# versao1b.net
KiCad netlist of a schematic drawn in EAGLE
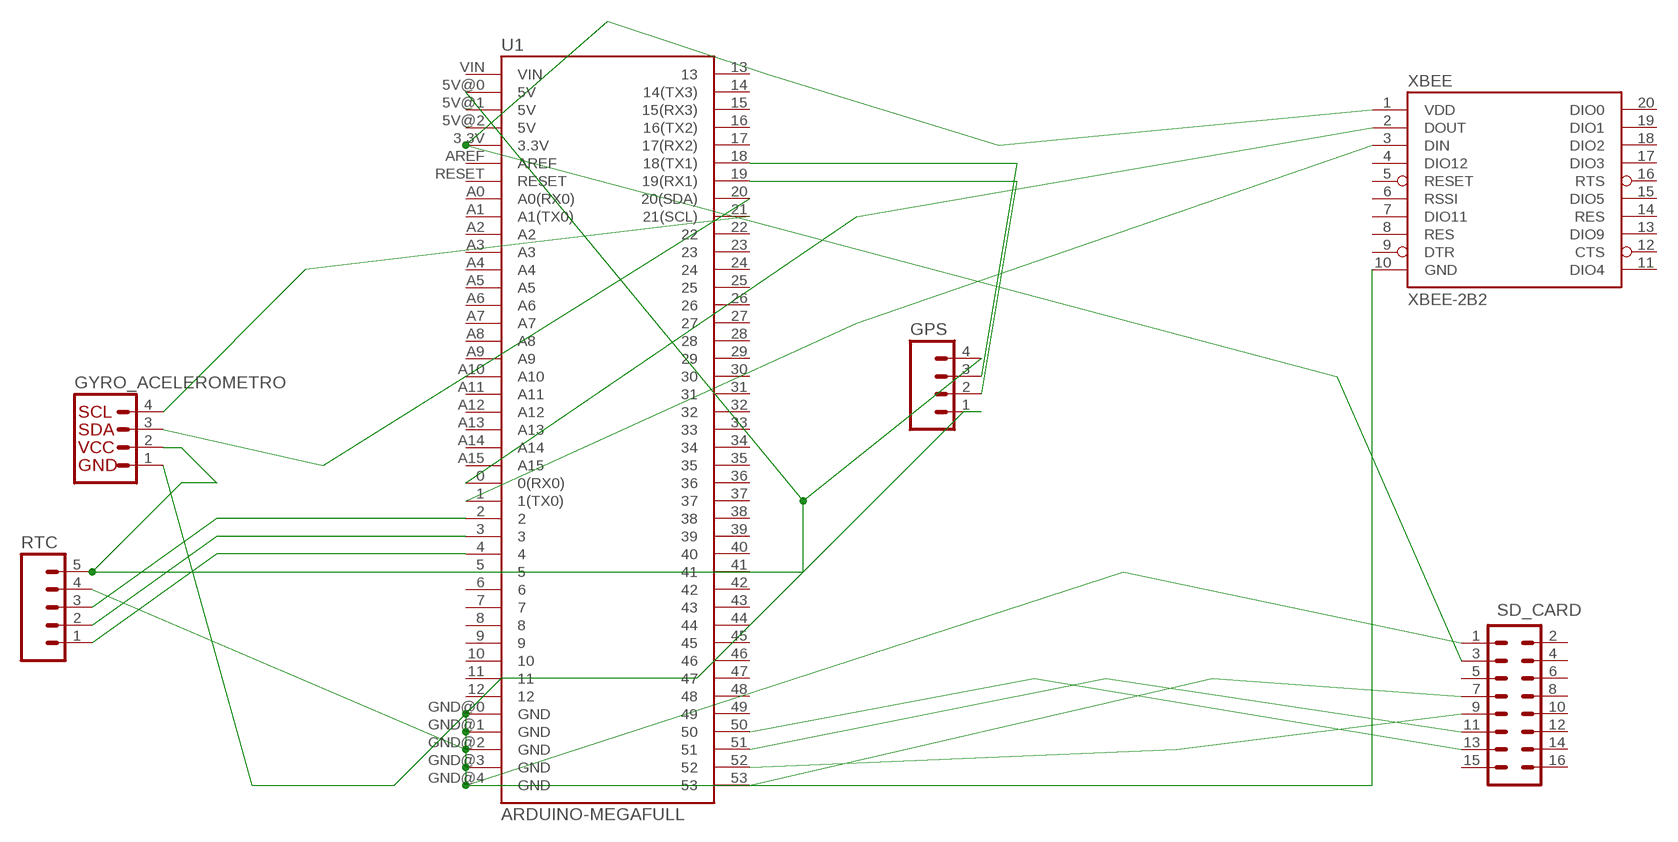
[diagram p0: schematic, sheet 1]

(export (version "E")
  (design (tool "Eeschema 10.0.6"))
  (components
    (comp (ref "GPS")
      (value "M04LOCK")
      (footprint "eagle-import:1X04_LOCK")
      (libsource (lib "eagle-import") (part "M04LOCK"))
    )
    (comp (ref "GYRO_ACELEROMETRO")
      (value "I2C_STANDARD")
      (footprint "eagle-import:1X04")
      (libsource (lib "eagle-import") (part "I2C_STANDARD"))
    )
    (comp (ref "RTC")
      (value "M05LOCK")
      (footprint "eagle-import:1X05_LOCK")
      (libsource (lib "eagle-import") (part "M05LOCK"))
    )
    (comp (ref "SD_CARD")
      (value "M08X2")
      (footprint "eagle-import:2X8")
      (libsource (lib "eagle-import") (part "M08X2"))
    )
    (comp (ref "U1")
      (value "ARDUINO-MEGAFULL")
      (footprint "eagle-import:ARDUINO_MEGA")
      (libsource (lib "eagle-import") (part "ARDUINO-MEGAFULL"))
    )
    (comp (ref "XBEE")
      (value "XBEE-2B2")
      (footprint "eagle-import:XBEE-SILK")
      (libsource (lib "eagle-import") (part "XBEE-2B2"))
    )
  )
  (nets
    (net (code "1") (name "Net-(GPS-Pad4)") (class "Default")
      (node (ref "GPS") (pin "4") (pinfunction "4_4") (pintype "passive"))
      (node (ref "GYRO_ACELEROMETRO") (pin "2") (pinfunction "2_2") (pintype "passive"))
      (node (ref "RTC") (pin "5") (pinfunction "5_5") (pintype "passive"))
      (node (ref "U1") (pin "5V@0") (pinfunction "5V_5V@0") (pintype "bidirectional"))
    )
    (net (code "2") (name "Net-(RTC-Pad1)") (class "Default")
      (node (ref "RTC") (pin "1") (pinfunction "1_1") (pintype "passive"))
      (node (ref "U1") (pin "4") (pinfunction "4_4") (pintype "bidirectional"))
    )
    (net (code "3") (name "Net-(RTC-Pad2)") (class "Default")
      (node (ref "RTC") (pin "2") (pinfunction "2_2") (pintype "passive"))
      (node (ref "U1") (pin "3") (pinfunction "3_3") (pintype "bidirectional"))
    )
    (net (code "4") (name "Net-(RTC-Pad3)") (class "Default")
      (node (ref "RTC") (pin "3") (pinfunction "3_3") (pintype "passive"))
      (node (ref "U1") (pin "2") (pinfunction "2_2") (pintype "bidirectional"))
    )
    (net (code "5") (name "Net-(SD_CARD-Pad7)") (class "Default")
      (node (ref "SD_CARD") (pin "7") (pinfunction "7_7") (pintype "passive"))
      (node (ref "U1") (pin "53") (pinfunction "53_53") (pintype "bidirectional"))
    )
    (net (code "6") (name "Net-(SD_CARD-Pad9)") (class "Default")
      (node (ref "SD_CARD") (pin "9") (pinfunction "9_9") (pintype "passive"))
      (node (ref "U1") (pin "52") (pinfunction "52_52") (pintype "bidirectional"))
    )
    (net (code "7") (name "Net-(SD_CARD-Pad11)") (class "Default")
      (node (ref "SD_CARD") (pin "11") (pinfunction "11_11") (pintype "passive"))
      (node (ref "U1") (pin "51") (pinfunction "51_51") (pintype "bidirectional"))
    )
    (net (code "8") (name "Net-(SD_CARD-Pad13)") (class "Default")
      (node (ref "SD_CARD") (pin "13") (pinfunction "13_13") (pintype "passive"))
      (node (ref "U1") (pin "50") (pinfunction "50_50") (pintype "bidirectional"))
    )
    (net (code "9") (name "Net-(U1-0(RX0))") (class "Default")
      (node (ref "U1") (pin "0") (pinfunction "0(RX0)_0") (pintype "bidirectional"))
      (node (ref "XBEE") (pin "2") (pinfunction "DOUT_2") (pintype "output"))
    )
    (net (code "10") (name "Net-(U1-1(TX0))") (class "Default")
      (node (ref "U1") (pin "1") (pinfunction "1(TX0)_1") (pintype "bidirectional"))
      (node (ref "XBEE") (pin "3") (pinfunction "DIN_3") (pintype "input"))
    )
    (net (code "11") (name "Net-(U1-18(TX1))") (class "Default")
      (node (ref "GPS") (pin "3") (pinfunction "3_3") (pintype "passive"))
      (node (ref "U1") (pin "18") (pinfunction "18(TX1)_18") (pintype "bidirectional"))
    )
    (net (code "12") (name "Net-(U1-19(RX1))") (class "Default")
      (node (ref "GPS") (pin "2") (pinfunction "2_2") (pintype "passive"))
      (node (ref "U1") (pin "19") (pinfunction "19(RX1)_19") (pintype "bidirectional"))
    )
    (net (code "13") (name "Net-(U1-20(SDA))") (class "Default")
      (node (ref "GYRO_ACELEROMETRO") (pin "3") (pinfunction "3_3") (pintype "passive"))
      (node (ref "U1") (pin "20") (pinfunction "20(SDA)_20") (pintype "bidirectional"))
    )
    (net (code "14") (name "Net-(U1-21(SCL))") (class "Default")
      (node (ref "GYRO_ACELEROMETRO") (pin "4") (pinfunction "4_4") (pintype "passive"))
      (node (ref "U1") (pin "21") (pinfunction "21(SCL)_21") (pintype "bidirectional"))
    )
    (net (code "15") (name "Net-(XBEE-GND)") (class "Default")
      (node (ref "GPS") (pin "1") (pinfunction "1_1") (pintype "passive"))
      (node (ref "GYRO_ACELEROMETRO") (pin "1") (pinfunction "1_1") (pintype "passive"))
      (node (ref "RTC") (pin "4") (pinfunction "4_4") (pintype "passive"))
      (node (ref "SD_CARD") (pin "1") (pinfunction "1_1") (pintype "passive"))
      (node (ref "U1") (pin "GND@0") (pinfunction "GND_GND@0") (pintype "bidirectional"))
      (node (ref "U1") (pin "GND@1") (pinfunction "GND_GND@1") (pintype "bidirectional"))
      (node (ref "U1") (pin "GND@2") (pinfunction "GND_GND@2") (pintype "bidirectional"))
      (node (ref "U1") (pin "GND@3") (pinfunction "GND_GND@3") (pintype "bidirectional"))
      (node (ref "U1") (pin "GND@4") (pinfunction "GND_GND@4") (pintype "bidirectional"))
      (node (ref "XBEE") (pin "10") (pinfunction "GND_10") (pintype "power_in"))
    )
    (net (code "16") (name "Net-(XBEE-VDD)") (class "Default")
      (node (ref "SD_CARD") (pin "3") (pinfunction "3_3") (pintype "passive"))
      (node (ref "U1") (pin "3.3V") (pinfunction "3.3V_3.3V") (pintype "bidirectional"))
      (node (ref "XBEE") (pin "1") (pinfunction "VDD_1") (pintype "power_in"))
    )
    (net (code "17") (name "unconnected-(SD_CARD-Pad2)") (class "Default")
      (node (ref "SD_CARD") (pin "2") (pinfunction "2_2") (pintype "passive"))
    )
    (net (code "18") (name "unconnected-(SD_CARD-Pad4)") (class "Default")
      (node (ref "SD_CARD") (pin "4") (pinfunction "4_4") (pintype "passive"))
    )
    (net (code "19") (name "unconnected-(SD_CARD-Pad5)") (class "Default")
      (node (ref "SD_CARD") (pin "5") (pinfunction "5_5") (pintype "passive"))
    )
    (net (code "20") (name "unconnected-(SD_CARD-Pad6)") (class "Default")
      (node (ref "SD_CARD") (pin "6") (pinfunction "6_6") (pintype "passive"))
    )
    (net (code "21") (name "unconnected-(SD_CARD-Pad8)") (class "Default")
      (node (ref "SD_CARD") (pin "8") (pinfunction "8_8") (pintype "passive"))
    )
    (net (code "22") (name "unconnected-(SD_CARD-Pad10)") (class "Default")
      (node (ref "SD_CARD") (pin "10") (pinfunction "10_10") (pintype "passive"))
    )
    (net (code "23") (name "unconnected-(SD_CARD-Pad12)") (class "Default")
      (node (ref "SD_CARD") (pin "12") (pinfunction "12_12") (pintype "passive"))
    )
    (net (code "24") (name "unconnected-(SD_CARD-Pad14)") (class "Default")
      (node (ref "SD_CARD") (pin "14") (pinfunction "14_14") (pintype "passive"))
    )
    (net (code "25") (name "unconnected-(SD_CARD-Pad15)") (class "Default")
      (node (ref "SD_CARD") (pin "15") (pinfunction "15_15") (pintype "passive"))
    )
    (net (code "26") (name "unconnected-(SD_CARD-Pad16)") (class "Default")
      (node (ref "SD_CARD") (pin "16") (pinfunction "16_16") (pintype "passive"))
    )
    (net (code "27") (name "unconnected-(U1-5V-Pad5V@1)") (class "Default")
      (node (ref "U1") (pin "5V@1") (pinfunction "5V_5V@1") (pintype "bidirectional"))
    )
    (net (code "28") (name "unconnected-(U1-5V-Pad5V@2)") (class "Default")
      (node (ref "U1") (pin "5V@2") (pinfunction "5V_5V@2") (pintype "bidirectional"))
    )
    (net (code "29") (name "unconnected-(U1-14(TX3)-Pad14)") (class "Default")
      (node (ref "U1") (pin "14") (pinfunction "14(TX3)_14") (pintype "bidirectional"))
    )
    (net (code "30") (name "unconnected-(U1-15(RX3)-Pad15)") (class "Default")
      (node (ref "U1") (pin "15") (pinfunction "15(RX3)_15") (pintype "bidirectional"))
    )
    (net (code "31") (name "unconnected-(U1-16(TX2)-Pad16)") (class "Default")
      (node (ref "U1") (pin "16") (pinfunction "16(TX2)_16") (pintype "bidirectional"))
    )
    (net (code "32") (name "unconnected-(U1-17(RX2)-Pad17)") (class "Default")
      (node (ref "U1") (pin "17") (pinfunction "17(RX2)_17") (pintype "bidirectional"))
    )
    (net (code "33") (name "unconnected-(U1-A0(RX0)-PadA0)") (class "Default")
      (node (ref "U1") (pin "A0") (pinfunction "A0(RX0)_A0") (pintype "bidirectional"))
    )
    (net (code "34") (name "unconnected-(U1-A1(TX0)-PadA1)") (class "Default")
      (node (ref "U1") (pin "A1") (pinfunction "A1(TX0)_A1") (pintype "bidirectional"))
    )
    (net (code "35") (name "unconnected-(U1-Pad5)") (class "Default")
      (node (ref "U1") (pin "5") (pinfunction "5_5") (pintype "bidirectional"))
    )
    (net (code "36") (name "unconnected-(U1-Pad6)") (class "Default")
      (node (ref "U1") (pin "6") (pinfunction "6_6") (pintype "bidirectional"))
    )
    (net (code "37") (name "unconnected-(U1-Pad7)") (class "Default")
      (node (ref "U1") (pin "7") (pinfunction "7_7") (pintype "bidirectional"))
    )
    (net (code "38") (name "unconnected-(U1-Pad8)") (class "Default")
      (node (ref "U1") (pin "8") (pinfunction "8_8") (pintype "bidirectional"))
    )
    (net (code "39") (name "unconnected-(U1-Pad9)") (class "Default")
      (node (ref "U1") (pin "9") (pinfunction "9_9") (pintype "bidirectional"))
    )
    (net (code "40") (name "unconnected-(U1-Pad10)") (class "Default")
      (node (ref "U1") (pin "10") (pinfunction "10_10") (pintype "bidirectional"))
    )
    (net (code "41") (name "unconnected-(U1-Pad11)") (class "Default")
      (node (ref "U1") (pin "11") (pinfunction "11_11") (pintype "bidirectional"))
    )
    (net (code "42") (name "unconnected-(U1-Pad12)") (class "Default")
      (node (ref "U1") (pin "12") (pinfunction "12_12") (pintype "bidirectional"))
    )
    (net (code "43") (name "unconnected-(U1-Pad13)") (class "Default")
      (node (ref "U1") (pin "13") (pinfunction "13_13") (pintype "bidirectional"))
    )
    (net (code "44") (name "unconnected-(U1-Pad22)") (class "Default")
      (node (ref "U1") (pin "22") (pinfunction "22_22") (pintype "bidirectional"))
    )
    (net (code "45") (name "unconnected-(U1-Pad23)") (class "Default")
      (node (ref "U1") (pin "23") (pinfunction "23_23") (pintype "bidirectional"))
    )
    (net (code "46") (name "unconnected-(U1-Pad24)") (class "Default")
      (node (ref "U1") (pin "24") (pinfunction "24_24") (pintype "bidirectional"))
    )
    (net (code "47") (name "unconnected-(U1-Pad25)") (class "Default")
      (node (ref "U1") (pin "25") (pinfunction "25_25") (pintype "bidirectional"))
    )
    (net (code "48") (name "unconnected-(U1-Pad26)") (class "Default")
      (node (ref "U1") (pin "26") (pinfunction "26_26") (pintype "bidirectional"))
    )
    (net (code "49") (name "unconnected-(U1-Pad27)") (class "Default")
      (node (ref "U1") (pin "27") (pinfunction "27_27") (pintype "bidirectional"))
    )
    (net (code "50") (name "unconnected-(U1-Pad28)") (class "Default")
      (node (ref "U1") (pin "28") (pinfunction "28_28") (pintype "bidirectional"))
    )
    (net (code "51") (name "unconnected-(U1-Pad29)") (class "Default")
      (node (ref "U1") (pin "29") (pinfunction "29_29") (pintype "bidirectional"))
    )
    (net (code "52") (name "unconnected-(U1-Pad30)") (class "Default")
      (node (ref "U1") (pin "30") (pinfunction "30_30") (pintype "bidirectional"))
    )
    (net (code "53") (name "unconnected-(U1-Pad31)") (class "Default")
      (node (ref "U1") (pin "31") (pinfunction "31_31") (pintype "bidirectional"))
    )
    (net (code "54") (name "unconnected-(U1-Pad32)") (class "Default")
      (node (ref "U1") (pin "32") (pinfunction "32_32") (pintype "bidirectional"))
    )
    (net (code "55") (name "unconnected-(U1-Pad33)") (class "Default")
      (node (ref "U1") (pin "33") (pinfunction "33_33") (pintype "bidirectional"))
    )
    (net (code "56") (name "unconnected-(U1-Pad34)") (class "Default")
      (node (ref "U1") (pin "34") (pinfunction "34_34") (pintype "bidirectional"))
    )
    (net (code "57") (name "unconnected-(U1-Pad35)") (class "Default")
      (node (ref "U1") (pin "35") (pinfunction "35_35") (pintype "bidirectional"))
    )
    (net (code "58") (name "unconnected-(U1-Pad36)") (class "Default")
      (node (ref "U1") (pin "36") (pinfunction "36_36") (pintype "bidirectional"))
    )
    (net (code "59") (name "unconnected-(U1-Pad37)") (class "Default")
      (node (ref "U1") (pin "37") (pinfunction "37_37") (pintype "bidirectional"))
    )
    (net (code "60") (name "unconnected-(U1-Pad38)") (class "Default")
      (node (ref "U1") (pin "38") (pinfunction "38_38") (pintype "bidirectional"))
    )
    (net (code "61") (name "unconnected-(U1-Pad39)") (class "Default")
      (node (ref "U1") (pin "39") (pinfunction "39_39") (pintype "bidirectional"))
    )
    (net (code "62") (name "unconnected-(U1-Pad40)") (class "Default")
      (node (ref "U1") (pin "40") (pinfunction "40_40") (pintype "bidirectional"))
    )
    (net (code "63") (name "unconnected-(U1-Pad41)") (class "Default")
      (node (ref "U1") (pin "41") (pinfunction "41_41") (pintype "bidirectional"))
    )
    (net (code "64") (name "unconnected-(U1-Pad42)") (class "Default")
      (node (ref "U1") (pin "42") (pinfunction "42_42") (pintype "bidirectional"))
    )
    (net (code "65") (name "unconnected-(U1-Pad43)") (class "Default")
      (node (ref "U1") (pin "43") (pinfunction "43_43") (pintype "bidirectional"))
    )
    (net (code "66") (name "unconnected-(U1-Pad44)") (class "Default")
      (node (ref "U1") (pin "44") (pinfunction "44_44") (pintype "bidirectional"))
    )
    (net (code "67") (name "unconnected-(U1-Pad45)") (class "Default")
      (node (ref "U1") (pin "45") (pinfunction "45_45") (pintype "bidirectional"))
    )
    (net (code "68") (name "unconnected-(U1-Pad46)") (class "Default")
      (node (ref "U1") (pin "46") (pinfunction "46_46") (pintype "bidirectional"))
    )
    (net (code "69") (name "unconnected-(U1-Pad47)") (class "Default")
      (node (ref "U1") (pin "47") (pinfunction "47_47") (pintype "bidirectional"))
    )
    (net (code "70") (name "unconnected-(U1-Pad48)") (class "Default")
      (node (ref "U1") (pin "48") (pinfunction "48_48") (pintype "bidirectional"))
    )
    (net (code "71") (name "unconnected-(U1-Pad49)") (class "Default")
      (node (ref "U1") (pin "49") (pinfunction "49_49") (pintype "bidirectional"))
    )
    (net (code "72") (name "unconnected-(U1-PadA2)") (class "Default")
      (node (ref "U1") (pin "A2") (pinfunction "A2_A2") (pintype "bidirectional"))
    )
    (net (code "73") (name "unconnected-(U1-PadA3)") (class "Default")
      (node (ref "U1") (pin "A3") (pinfunction "A3_A3") (pintype "bidirectional"))
    )
    (net (code "74") (name "unconnected-(U1-PadA4)") (class "Default")
      (node (ref "U1") (pin "A4") (pinfunction "A4_A4") (pintype "bidirectional"))
    )
    (net (code "75") (name "unconnected-(U1-PadA5)") (class "Default")
      (node (ref "U1") (pin "A5") (pinfunction "A5_A5") (pintype "bidirectional"))
    )
    (net (code "76") (name "unconnected-(U1-PadA6)") (class "Default")
      (node (ref "U1") (pin "A6") (pinfunction "A6_A6") (pintype "bidirectional"))
    )
    (net (code "77") (name "unconnected-(U1-PadA7)") (class "Default")
      (node (ref "U1") (pin "A7") (pinfunction "A7_A7") (pintype "bidirectional"))
    )
    (net (code "78") (name "unconnected-(U1-PadA8)") (class "Default")
      (node (ref "U1") (pin "A8") (pinfunction "A8_A8") (pintype "bidirectional"))
    )
    (net (code "79") (name "unconnected-(U1-PadA9)") (class "Default")
      (node (ref "U1") (pin "A9") (pinfunction "A9_A9") (pintype "bidirectional"))
    )
    (net (code "80") (name "unconnected-(U1-PadA10)") (class "Default")
      (node (ref "U1") (pin "A10") (pinfunction "A10_A10") (pintype "bidirectional"))
    )
    (net (code "81") (name "unconnected-(U1-PadA11)") (class "Default")
      (node (ref "U1") (pin "A11") (pinfunction "A11_A11") (pintype "bidirectional"))
    )
    (net (code "82") (name "unconnected-(U1-PadA12)") (class "Default")
      (node (ref "U1") (pin "A12") (pinfunction "A12_A12") (pintype "bidirectional"))
    )
    (net (code "83") (name "unconnected-(U1-PadA13)") (class "Default")
      (node (ref "U1") (pin "A13") (pinfunction "A13_A13") (pintype "bidirectional"))
    )
    (net (code "84") (name "unconnected-(U1-PadA14)") (class "Default")
      (node (ref "U1") (pin "A14") (pinfunction "A14_A14") (pintype "bidirectional"))
    )
    (net (code "85") (name "unconnected-(U1-PadA15)") (class "Default")
      (node (ref "U1") (pin "A15") (pinfunction "A15_A15") (pintype "bidirectional"))
    )
    (net (code "86") (name "unconnected-(U1-PadAREF)") (class "Default")
      (node (ref "U1") (pin "AREF") (pinfunction "AREF_AREF") (pintype "bidirectional"))
    )
    (net (code "87") (name "unconnected-(U1-PadRESET)") (class "Default")
      (node (ref "U1") (pin "RESET") (pinfunction "RESET_RESET") (pintype "bidirectional"))
    )
    (net (code "88") (name "unconnected-(U1-PadVIN)") (class "Default")
      (node (ref "U1") (pin "VIN") (pinfunction "VIN_VIN") (pintype "bidirectional"))
    )
    (net (code "89") (name "unconnected-(XBEE-CTS-Pad12)") (class "Default")
      (node (ref "XBEE") (pin "12") (pinfunction "CTS_12") (pintype "output"))
    )
    (net (code "90") (name "unconnected-(XBEE-DIO0-Pad20)") (class "Default")
      (node (ref "XBEE") (pin "20") (pinfunction "DIO0_20") (pintype "bidirectional"))
    )
    (net (code "91") (name "unconnected-(XBEE-DIO1-Pad19)") (class "Default")
      (node (ref "XBEE") (pin "19") (pinfunction "DIO1_19") (pintype "bidirectional"))
    )
    (net (code "92") (name "unconnected-(XBEE-DIO2-Pad18)") (class "Default")
      (node (ref "XBEE") (pin "18") (pinfunction "DIO2_18") (pintype "bidirectional"))
    )
    (net (code "93") (name "unconnected-(XBEE-DIO3-Pad17)") (class "Default")
      (node (ref "XBEE") (pin "17") (pinfunction "DIO3_17") (pintype "bidirectional"))
    )
    (net (code "94") (name "unconnected-(XBEE-DIO4-Pad11)") (class "Default")
      (node (ref "XBEE") (pin "11") (pinfunction "DIO4_11") (pintype "bidirectional"))
    )
    (net (code "95") (name "unconnected-(XBEE-DIO5-Pad15)") (class "Default")
      (node (ref "XBEE") (pin "15") (pinfunction "DIO5_15") (pintype "bidirectional"))
    )
    (net (code "96") (name "unconnected-(XBEE-DIO9-Pad13)") (class "Default")
      (node (ref "XBEE") (pin "13") (pinfunction "DIO9_13") (pintype "bidirectional"))
    )
    (net (code "97") (name "unconnected-(XBEE-DIO11-Pad7)") (class "Default")
      (node (ref "XBEE") (pin "7") (pinfunction "DIO11_7") (pintype "bidirectional"))
    )
    (net (code "98") (name "unconnected-(XBEE-DIO12-Pad4)") (class "Default")
      (node (ref "XBEE") (pin "4") (pinfunction "DIO12_4") (pintype "bidirectional"))
    )
    (net (code "99") (name "unconnected-(XBEE-DTR-Pad9)") (class "Default")
      (node (ref "XBEE") (pin "9") (pinfunction "DTR_9") (pintype "bidirectional"))
    )
    (net (code "100") (name "unconnected-(XBEE-RES-Pad8)") (class "Default")
      (node (ref "XBEE") (pin "8") (pinfunction "RES_8") (pintype "bidirectional"))
    )
    (net (code "101") (name "unconnected-(XBEE-RES-Pad14)") (class "Default")
      (node (ref "XBEE") (pin "14") (pinfunction "RES_14") (pintype "bidirectional"))
    )
    (net (code "102") (name "unconnected-(XBEE-RESET-Pad5)") (class "Default")
      (node (ref "XBEE") (pin "5") (pinfunction "RESET_5") (pintype "input"))
    )
    (net (code "103") (name "unconnected-(XBEE-RSSI-Pad6)") (class "Default")
      (node (ref "XBEE") (pin "6") (pinfunction "RSSI_6") (pintype "bidirectional"))
    )
    (net (code "104") (name "unconnected-(XBEE-RTS-Pad16)") (class "Default")
      (node (ref "XBEE") (pin "16") (pinfunction "RTS_16") (pintype "input"))
    )
  )
)
